# Fri3D_2020_Doodles.net
KiCad netlist of a schematic drawn in Altium Designer
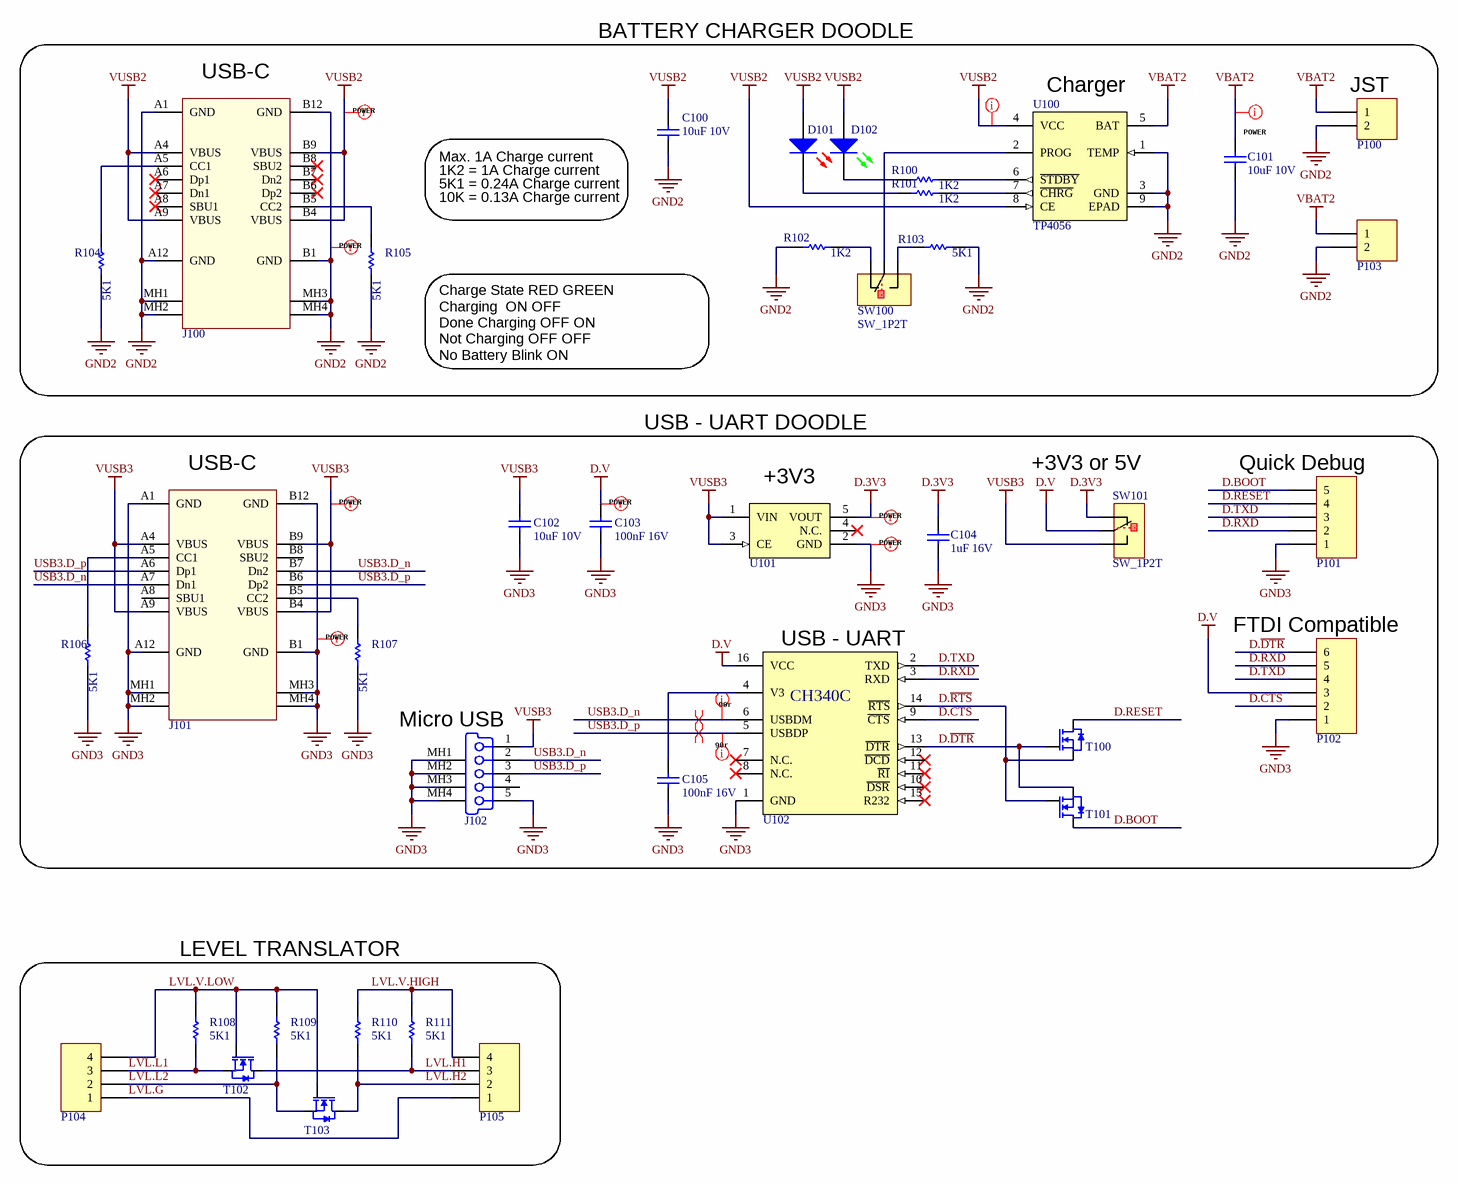
[diagram p0: Fri3D_2020_Doodles.SchDoc]

(export (version "E")
  (design (tool "Eeschema 10.0.6"))
  (components
    (comp (ref "C100")
      (value "10uF 10V")
      (footprint "C0805_N")
      (description "Capacitor Ceramic")
      (fields (field (name "Comment") "CAP_CERAMIC"))
      (libsource (lib "Phyx_Components") (part "CAP_CERAMIC"))
    )
    (comp (ref "C101")
      (value "10uF 10V")
      (footprint "C0805_N")
      (description "Capacitor Ceramic")
      (fields (field (name "Comment") "CAP_CERAMIC"))
      (libsource (lib "Phyx_Components") (part "CAP_CERAMIC"))
    )
    (comp (ref "C102")
      (value "10uF 10V")
      (footprint "C0805_N")
      (description "Capacitor Ceramic")
      (fields (field (name "Comment") "CAP_CERAMIC"))
      (libsource (lib "Phyx_Components") (part "CAP_CERAMIC"))
    )
    (comp (ref "C103")
      (value "100nF 16V")
      (footprint "C0603_N")
      (description "Capacitor Ceramic")
      (libsource (lib "Phyx_Components") (part "CAP_CERAMIC"))
    )
    (comp (ref "C104")
      (value "1uF 16V")
      (footprint "C0603_N")
      (description "Capacitor Ceramic")
      (fields (field (name "Comment") "CAP_CERAMIC"))
      (libsource (lib "Phyx_Components") (part "CAP_CERAMIC"))
    )
    (comp (ref "C105")
      (value "100nF 16V")
      (footprint "C0603_N")
      (description "Capacitor Ceramic")
      (libsource (lib "Phyx_Components") (part "CAP_CERAMIC"))
    )
    (comp (ref "D101")
      (value "Default 0805 Red LED")
      (footprint "LED_0805_RD")
      (description "=Description")
      (libsource (lib "Phyx_Components") (part "LED_RED"))
    )
    (comp (ref "D102")
      (value "Default 0805 Green LED")
      (footprint "LED_0805_GR")
      (description "=Description")
      (libsource (lib "Phyx_Components") (part "LED_GREEN"))
    )
    (comp (ref "J100")
      (value "USB 2.0 C Reversible Receptacle Horizontal")
      (footprint "HRO_TYPE-C-31-M-12")
      (libsource (lib "Phyx_Components") (part "USB_C_16_4"))
    )
    (comp (ref "J101")
      (value "USB 2.0 C Reversible Receptacle Horizontal")
      (footprint "HRO_TYPE-C-31-M-12")
      (libsource (lib "Phyx_Components") (part "USB_C_16_4"))
    )
    (comp (ref "J102")
      (value "XKB U254-051T-4BH81-S2S Micro USB")
      (footprint "XKB_U254-051T-4BH81-S2S")
      (libsource (lib "Phyx_Components") (part "USB_OTG_Mini-B"))
    )
    (comp (ref "P100")
      (value "Header 2.0mm Shrouded 2")
      (footprint "WE_620102131822")
      (libsource (lib "Phyx_Components") (part "Header 2"))
    )
    (comp (ref "P101")
      (value "Header 1.0mm RA Shrouded 5")
      (footprint "WE_665105131822")
      (libsource (lib "Phyx_Components") (part "Header 5"))
    )
    (comp (ref "P102")
      (value "Header 6")
      (footprint "HDR1X6")
      (libsource (lib "Phyx_Components") (part "Header 6"))
    )
    (comp (ref "P103")
      (value "Header 2")
      (footprint "HDR1X2")
      (libsource (lib "Phyx_Components") (part "Header 2"))
    )
    (comp (ref "P104")
      (value "Header 4")
      (footprint "HDR1X4")
      (libsource (lib "Phyx_Components") (part "Header 4"))
    )
    (comp (ref "P105") (value "Header 4") (footprint "HDR1X4") (libsource (lib "") (part "Header 4_1")))
    (comp (ref "R100")
      (value "1K2")
      (footprint "R0603_N")
      (fields (field (name "Comment") "RESISTOR"))
      (libsource (lib "Phyx_Components") (part "RESISTOR"))
    )
    (comp (ref "R101")
      (value "1K2")
      (footprint "R0603_N")
      (fields (field (name "Comment") "RESISTOR"))
      (libsource (lib "Phyx_Components") (part "RESISTOR"))
    )
    (comp (ref "R102")
      (value "1K2")
      (footprint "R0603_N")
      (fields (field (name "Comment") "RESISTOR"))
      (libsource (lib "Phyx_Components") (part "RESISTOR"))
    )
    (comp (ref "R103")
      (value "5K1")
      (footprint "R0603_N")
      (fields (field (name "Comment") "RESISTOR"))
      (libsource (lib "Phyx_Components") (part "RESISTOR"))
    )
    (comp (ref "R104")
      (value "5K1")
      (footprint "R0603_N")
      (fields (field (name "Comment") "RESISTOR"))
      (libsource (lib "Phyx_Components") (part "RESISTOR"))
    )
    (comp (ref "R105")
      (value "5K1")
      (footprint "R0603_N")
      (fields (field (name "Comment") "RESISTOR"))
      (libsource (lib "Phyx_Components") (part "RESISTOR"))
    )
    (comp (ref "R106")
      (value "5K1")
      (footprint "R0603_N")
      (fields (field (name "Comment") "RESISTOR"))
      (libsource (lib "Phyx_Components") (part "RESISTOR"))
    )
    (comp (ref "R107")
      (value "5K1")
      (footprint "R0603_N")
      (fields (field (name "Comment") "RESISTOR"))
      (libsource (lib "Phyx_Components") (part "RESISTOR"))
    )
    (comp (ref "R108")
      (value "5K1")
      (footprint "R0603_N")
      (fields (field (name "Comment") "RESISTOR"))
      (libsource (lib "Phyx_Components") (part "RESISTOR"))
    )
    (comp (ref "R109")
      (value "5K1")
      (footprint "R0603_N")
      (fields (field (name "Comment") "RESISTOR"))
      (libsource (lib "Phyx_Components") (part "RESISTOR"))
    )
    (comp (ref "R110")
      (value "5K1")
      (footprint "R0603_N")
      (fields (field (name "Comment") "RESISTOR"))
      (libsource (lib "Phyx_Components") (part "RESISTOR"))
    )
    (comp (ref "R111")
      (value "5K1")
      (footprint "R0603_N")
      (fields (field (name "Comment") "RESISTOR"))
      (libsource (lib "Phyx_Components") (part "RESISTOR"))
    )
    (comp (ref "SW100")
      (value "SW_1P2T")
      (footprint "WE_450404015514")
      (libsource (lib "Phyx_Components") (part "SW_1P2T"))
    )
    (comp (ref "SW101")
      (value "SW_1P2T")
      (footprint "WE_450404015514")
      (libsource (lib "") (part "SW_1P2T_1"))
    )
    (comp (ref "T100")
      (value "0.2A N-Ch MOSFET Vgs 3.2")
      (footprint "SOT23-3")
      (libsource (lib "Phyx_Components") (part "N_MOSFET_GSD"))
    )
    (comp (ref "T101")
      (value "0.2A N-Ch MOSFET Vgs 3.2")
      (footprint "SOT23-3")
      (libsource (lib "Phyx_Components") (part "N_MOSFET_GSD"))
    )
    (comp (ref "T102")
      (value "0.2A N-Ch MOSFET Vgs 3.2")
      (footprint "SOT23-3")
      (libsource (lib "Phyx_Components") (part "N_MOSFET_GSD"))
    )
    (comp (ref "T103")
      (value "0.2A N-Ch MOSFET Vgs 3.2")
      (footprint "SOT23-3")
      (libsource (lib "Phyx_Components") (part "N_MOSFET_GSD"))
    )
    (comp (ref "U100")
      (value "TP4056")
      (footprint "SOIC_N_8_TH")
      (description "=Description")
      (fields (field (name "Comment") "Single Cell LiIon charger max 1A"))
      (libsource (lib "Phyx_Components") (part "TP4056"))
    )
    (comp (ref "U101")
      (value "3V3 LDO 700mA 50mV")
      (footprint "SOT23-5")
      (description "=Designator")
      (libsource (lib "Phyx_Components") (part "XC6210_SOT"))
    )
    (comp (ref "U102")
      (value "USB to full UART with internal crystal")
      (footprint "SOIC_N_16")
      (description "=Description")
      (libsource (lib "Phyx_Components") (part "CH340C"))
    )
  )
  (nets
    (net (code "1") (name "/D.BOOT") (class "Default")
      (node (ref "P101") (pin "5") (pinfunction "5_5") (pintype "passive"))
      (node (ref "T101") (pin "3") (pinfunction "D_3") (pintype "passive"))
    )
    (net (code "2") (name "/D.RESET") (class "Default")
      (node (ref "P101") (pin "4") (pinfunction "4_4") (pintype "passive"))
      (node (ref "T100") (pin "3") (pinfunction "D_3") (pintype "passive"))
    )
    (net (code "3") (name "/D.RXD") (class "Default")
      (node (ref "P101") (pin "2") (pinfunction "2_2") (pintype "passive"))
      (node (ref "P102") (pin "5") (pinfunction "5_5") (pintype "passive"))
      (node (ref "U102") (pin "3") (pinfunction "RXD_3") (pintype "input"))
    )
    (net (code "4") (name "/D.TXD") (class "Default")
      (node (ref "P101") (pin "3") (pinfunction "3_3") (pintype "passive"))
      (node (ref "P102") (pin "4") (pinfunction "4_4") (pintype "passive"))
      (node (ref "U102") (pin "2") (pinfunction "TXD_2") (pintype "output"))
    )
    (net (code "5") (name "/D.~{CTS}") (class "Default")
      (node (ref "P102") (pin "2") (pinfunction "2_2") (pintype "passive"))
      (node (ref "U102") (pin "9") (pinfunction "~{CTS}_9") (pintype "input"))
    )
    (net (code "6") (name "/D.~{DTR}") (class "Default")
      (node (ref "P102") (pin "6") (pinfunction "6_6") (pintype "passive"))
      (node (ref "T100") (pin "1") (pinfunction "G_1") (pintype "passive"))
      (node (ref "T101") (pin "2") (pinfunction "S_2") (pintype "passive"))
      (node (ref "U102") (pin "13") (pinfunction "~{DTR}_13") (pintype "output"))
    )
    (net (code "7") (name "/D.~{RTS}") (class "Default")
      (node (ref "T100") (pin "2") (pinfunction "S_2") (pintype "passive"))
      (node (ref "T101") (pin "1") (pinfunction "G_1") (pintype "passive"))
      (node (ref "U102") (pin "14") (pinfunction "~{RTS}_14") (pintype "output"))
    )
    (net (code "8") (name "/LVL.G") (class "Default")
      (node (ref "P104") (pin "1") (pinfunction "1_1") (pintype "passive"))
      (node (ref "P105") (pin "1") (pinfunction "1_1") (pintype "passive"))
    )
    (net (code "9") (name "/LVL.H1") (class "Default")
      (node (ref "P105") (pin "3") (pinfunction "3_3") (pintype "passive"))
      (node (ref "R111") (pin "2") (pinfunction "2_2") (pintype "passive"))
      (node (ref "T102") (pin "3") (pinfunction "D_3") (pintype "passive"))
    )
    (net (code "10") (name "/LVL.H2") (class "Default")
      (node (ref "P105") (pin "2") (pinfunction "2_2") (pintype "passive"))
      (node (ref "R110") (pin "2") (pinfunction "2_2") (pintype "passive"))
      (node (ref "T103") (pin "3") (pinfunction "D_3") (pintype "passive"))
    )
    (net (code "11") (name "/LVL.L1") (class "Default")
      (node (ref "P104") (pin "3") (pinfunction "3_3") (pintype "passive"))
      (node (ref "R108") (pin "2") (pinfunction "2_2") (pintype "passive"))
      (node (ref "T102") (pin "2") (pinfunction "S_2") (pintype "passive"))
    )
    (net (code "12") (name "/LVL.L2") (class "Default")
      (node (ref "P104") (pin "2") (pinfunction "2_2") (pintype "passive"))
      (node (ref "R109") (pin "2") (pinfunction "2_2") (pintype "passive"))
      (node (ref "T103") (pin "2") (pinfunction "S_2") (pintype "passive"))
    )
    (net (code "13") (name "/LVL.V.HIGH") (class "Default")
      (node (ref "P105") (pin "4") (pinfunction "4_4") (pintype "passive"))
      (node (ref "R110") (pin "1") (pinfunction "1_1") (pintype "passive"))
      (node (ref "R111") (pin "1") (pinfunction "1_1") (pintype "passive"))
    )
    (net (code "14") (name "/LVL.V.LOW") (class "Default")
      (node (ref "P104") (pin "4") (pinfunction "4_4") (pintype "passive"))
      (node (ref "R108") (pin "1") (pinfunction "1_1") (pintype "passive"))
      (node (ref "R109") (pin "1") (pinfunction "1_1") (pintype "passive"))
      (node (ref "T102") (pin "1") (pinfunction "G_1") (pintype "passive"))
      (node (ref "T103") (pin "1") (pinfunction "G_1") (pintype "passive"))
    )
    (net (code "15") (name "/USB3.D_n") (class "Default")
      (node (ref "J101") (pin "A7") (pinfunction "Dn1_A7") (pintype "passive"))
      (node (ref "J101") (pin "B7") (pinfunction "Dn2_B7") (pintype "passive"))
      (node (ref "J102") (pin "2") (pinfunction "D-_2") (pintype "passive"))
      (node (ref "U102") (pin "6") (pinfunction "USBDM_6") (pintype "passive"))
    )
    (net (code "16") (name "/USB3.D_p") (class "Default")
      (node (ref "J101") (pin "A6") (pinfunction "Dp1_A6") (pintype "passive"))
      (node (ref "J101") (pin "B6") (pinfunction "Dp2_B6") (pintype "passive"))
      (node (ref "J102") (pin "3") (pinfunction "D+_3") (pintype "passive"))
      (node (ref "U102") (pin "5") (pinfunction "USBDP_5") (pintype "passive"))
    )
    (net (code "17") (name "D.3V3") (class "Default")
      (node (ref "C104") (pin "1") (pinfunction "1_1") (pintype "passive"))
      (node (ref "SW101") (pin "1") (pinfunction "1_1") (pintype "passive"))
      (node (ref "U101") (pin "5") (pinfunction "VOUT_5") (pintype "power_in"))
    )
    (net (code "18") (name "D.V") (class "Default")
      (node (ref "C103") (pin "1") (pinfunction "1_1") (pintype "passive"))
      (node (ref "P102") (pin "3") (pinfunction "3_3") (pintype "passive"))
      (node (ref "SW101") (pin "2") (pinfunction "2_2") (pintype "passive"))
      (node (ref "U102") (pin "16") (pinfunction "VCC_16") (pintype "power_in"))
    )
    (net (code "19") (name "GND2") (class "Default")
      (node (ref "C100") (pin "2") (pinfunction "2_2") (pintype "passive"))
      (node (ref "C101") (pin "2") (pinfunction "2_2") (pintype "passive"))
      (node (ref "J100") (pin "A1") (pinfunction "GND_A1") (pintype "passive"))
      (node (ref "J100") (pin "A12") (pinfunction "GND_A12") (pintype "passive"))
      (node (ref "J100") (pin "B1") (pinfunction "GND_B1") (pintype "passive"))
      (node (ref "J100") (pin "B12") (pinfunction "GND_B12") (pintype "passive"))
      (node (ref "J100") (pin "MH1") (pinfunction "Tab_MH1") (pintype "passive"))
      (node (ref "J100") (pin "MH2") (pinfunction "Tab_MH2") (pintype "passive"))
      (node (ref "J100") (pin "MH3") (pinfunction "Tab_MH3") (pintype "passive"))
      (node (ref "J100") (pin "MH4") (pinfunction "Tab_MH4") (pintype "passive"))
      (node (ref "P100") (pin "2") (pinfunction "2_2") (pintype "passive"))
      (node (ref "P103") (pin "2") (pinfunction "2_2") (pintype "passive"))
      (node (ref "R102") (pin "2") (pinfunction "2_2") (pintype "passive"))
      (node (ref "R103") (pin "2") (pinfunction "2_2") (pintype "passive"))
      (node (ref "R104") (pin "2") (pinfunction "2_2") (pintype "passive"))
      (node (ref "R105") (pin "2") (pinfunction "2_2") (pintype "passive"))
      (node (ref "U100") (pin "1") (pinfunction "TEMP_1") (pintype "input"))
      (node (ref "U100") (pin "3") (pinfunction "GND_3") (pintype "power_in"))
      (node (ref "U100") (pin "9") (pinfunction "EPAD_9") (pintype "power_in"))
    )
    (net (code "20") (name "GND3") (class "Default")
      (node (ref "C102") (pin "2") (pinfunction "2_2") (pintype "passive"))
      (node (ref "C103") (pin "2") (pinfunction "2_2") (pintype "passive"))
      (node (ref "C104") (pin "2") (pinfunction "2_2") (pintype "passive"))
      (node (ref "C105") (pin "2") (pinfunction "2_2") (pintype "passive"))
      (node (ref "J101") (pin "A1") (pinfunction "GND_A1") (pintype "passive"))
      (node (ref "J101") (pin "A12") (pinfunction "GND_A12") (pintype "passive"))
      (node (ref "J101") (pin "B1") (pinfunction "GND_B1") (pintype "passive"))
      (node (ref "J101") (pin "B12") (pinfunction "GND_B12") (pintype "passive"))
      (node (ref "J101") (pin "MH1") (pinfunction "Tab_MH1") (pintype "passive"))
      (node (ref "J101") (pin "MH2") (pinfunction "Tab_MH2") (pintype "passive"))
      (node (ref "J101") (pin "MH3") (pinfunction "Tab_MH3") (pintype "passive"))
      (node (ref "J101") (pin "MH4") (pinfunction "Tab_MH4") (pintype "passive"))
      (node (ref "J102") (pin "5") (pinfunction "GND_5") (pintype "passive"))
      (node (ref "J102") (pin "MH1") (pinfunction "Tab_MH1") (pintype "passive"))
      (node (ref "J102") (pin "MH2") (pinfunction "Tab_MH2") (pintype "passive"))
      (node (ref "J102") (pin "MH3") (pinfunction "Tab_MH3") (pintype "passive"))
      (node (ref "J102") (pin "MH4") (pinfunction "Tab_MH4") (pintype "passive"))
      (node (ref "P101") (pin "1") (pinfunction "1_1") (pintype "passive"))
      (node (ref "P102") (pin "1") (pinfunction "1_1") (pintype "passive"))
      (node (ref "R106") (pin "2") (pinfunction "2_2") (pintype "passive"))
      (node (ref "R107") (pin "2") (pinfunction "2_2") (pintype "passive"))
      (node (ref "U101") (pin "2") (pinfunction "GND_2") (pintype "power_in"))
      (node (ref "U102") (pin "1") (pinfunction "GND_1") (pintype "power_in"))
    )
    (net (code "21") (name "Net-(D101-K)") (class "Default")
      (node (ref "D101") (pin "2") (pinfunction "K_2") (pintype "passive"))
      (node (ref "R101") (pin "1") (pinfunction "1_1") (pintype "passive"))
    )
    (net (code "22") (name "Net-(D102-K)") (class "Default")
      (node (ref "D102") (pin "2") (pinfunction "K_2") (pintype "passive"))
      (node (ref "R100") (pin "1") (pinfunction "1_1") (pintype "passive"))
    )
    (net (code "23") (name "Net-(J100-CC1)") (class "Default")
      (node (ref "J100") (pin "A5") (pinfunction "CC1_A5") (pintype "passive"))
      (node (ref "R104") (pin "1") (pinfunction "1_1") (pintype "passive"))
    )
    (net (code "24") (name "Net-(J100-CC2)") (class "Default")
      (node (ref "J100") (pin "B5") (pinfunction "CC2_B5") (pintype "passive"))
      (node (ref "R105") (pin "1") (pinfunction "1_1") (pintype "passive"))
    )
    (net (code "25") (name "Net-(J101-CC1)") (class "Default")
      (node (ref "J101") (pin "A5") (pinfunction "CC1_A5") (pintype "passive"))
      (node (ref "R106") (pin "1") (pinfunction "1_1") (pintype "passive"))
    )
    (net (code "26") (name "Net-(J101-CC2)") (class "Default")
      (node (ref "J101") (pin "B5") (pinfunction "CC2_B5") (pintype "passive"))
      (node (ref "R107") (pin "1") (pinfunction "1_1") (pintype "passive"))
    )
    (net (code "27") (name "Net-(R102-Pad1)") (class "Default")
      (node (ref "R102") (pin "1") (pinfunction "1_1") (pintype "passive"))
      (node (ref "SW100") (pin "1") (pinfunction "1_1") (pintype "passive"))
    )
    (net (code "28") (name "Net-(R103-Pad1)") (class "Default")
      (node (ref "R103") (pin "1") (pinfunction "1_1") (pintype "passive"))
      (node (ref "SW100") (pin "3") (pinfunction "3_3") (pintype "passive"))
    )
    (net (code "29") (name "Net-(U100-PROG)") (class "Default")
      (node (ref "SW100") (pin "2") (pinfunction "2_2") (pintype "passive"))
      (node (ref "U100") (pin "2") (pinfunction "PROG_2") (pintype "passive"))
    )
    (net (code "30") (name "Net-(U100-~{CHRG})") (class "Default")
      (node (ref "R101") (pin "2") (pinfunction "2_2") (pintype "passive"))
      (node (ref "U100") (pin "7") (pinfunction "~{CHRG}_7") (pintype "output"))
    )
    (net (code "31") (name "Net-(U100-~{STDBY})") (class "Default")
      (node (ref "R100") (pin "2") (pinfunction "2_2") (pintype "passive"))
      (node (ref "U100") (pin "6") (pinfunction "~{STDBY}_6") (pintype "output"))
    )
    (net (code "32") (name "Net-(U102-V3)") (class "Default")
      (node (ref "C105") (pin "1") (pinfunction "1_1") (pintype "passive"))
      (node (ref "U102") (pin "4") (pinfunction "V3_4") (pintype "power_in"))
    )
    (net (code "33") (name "VBAT2") (class "Default")
      (node (ref "C101") (pin "1") (pinfunction "1_1") (pintype "passive"))
      (node (ref "P100") (pin "1") (pinfunction "1_1") (pintype "passive"))
      (node (ref "P103") (pin "1") (pinfunction "1_1") (pintype "passive"))
      (node (ref "U100") (pin "5") (pinfunction "BAT_5") (pintype "power_in"))
    )
    (net (code "34") (name "VUSB2") (class "Default")
      (node (ref "C100") (pin "1") (pinfunction "1_1") (pintype "passive"))
      (node (ref "D101") (pin "1") (pinfunction "A_1") (pintype "passive"))
      (node (ref "D102") (pin "1") (pinfunction "A_1") (pintype "passive"))
      (node (ref "J100") (pin "A4") (pinfunction "VBUS_A4") (pintype "passive"))
      (node (ref "J100") (pin "A9") (pinfunction "VBUS_A9") (pintype "passive"))
      (node (ref "J100") (pin "B4") (pinfunction "VBUS_B4") (pintype "passive"))
      (node (ref "J100") (pin "B9") (pinfunction "VBUS_B9") (pintype "passive"))
      (node (ref "U100") (pin "4") (pinfunction "VCC_4") (pintype "power_in"))
      (node (ref "U100") (pin "8") (pinfunction "CE_8") (pintype "input"))
    )
    (net (code "35") (name "VUSB3") (class "Default")
      (node (ref "C102") (pin "1") (pinfunction "1_1") (pintype "passive"))
      (node (ref "J101") (pin "A4") (pinfunction "VBUS_A4") (pintype "passive"))
      (node (ref "J101") (pin "A9") (pinfunction "VBUS_A9") (pintype "passive"))
      (node (ref "J101") (pin "B4") (pinfunction "VBUS_B4") (pintype "passive"))
      (node (ref "J101") (pin "B9") (pinfunction "VBUS_B9") (pintype "passive"))
      (node (ref "J102") (pin "1") (pinfunction "V_BUS_(5V)_1") (pintype "passive"))
      (node (ref "SW101") (pin "3") (pinfunction "3_3") (pintype "passive"))
      (node (ref "U101") (pin "1") (pinfunction "VIN_1") (pintype "power_in"))
      (node (ref "U101") (pin "3") (pinfunction "CE_3") (pintype "input"))
    )
    (net (code "36") (name "unconnected-(J100-Dn1-PadA7)") (class "Default")
      (node (ref "J100") (pin "A7") (pinfunction "Dn1_A7") (pintype "passive+no_connect"))
    )
    (net (code "37") (name "unconnected-(J100-Dn2-PadB7)") (class "Default")
      (node (ref "J100") (pin "B7") (pinfunction "Dn2_B7") (pintype "passive+no_connect"))
    )
    (net (code "38") (name "unconnected-(J100-Dp1-PadA6)") (class "Default")
      (node (ref "J100") (pin "A6") (pinfunction "Dp1_A6") (pintype "passive+no_connect"))
    )
    (net (code "39") (name "unconnected-(J100-Dp2-PadB6)") (class "Default")
      (node (ref "J100") (pin "B6") (pinfunction "Dp2_B6") (pintype "passive+no_connect"))
    )
    (net (code "40") (name "unconnected-(J100-SBU1-PadA8)") (class "Default")
      (node (ref "J100") (pin "A8") (pinfunction "SBU1_A8") (pintype "passive+no_connect"))
    )
    (net (code "41") (name "unconnected-(J100-SBU2-PadB8)") (class "Default")
      (node (ref "J100") (pin "B8") (pinfunction "SBU2_B8") (pintype "passive+no_connect"))
    )
    (net (code "42") (name "unconnected-(J101-SBU1-PadA8)") (class "Default")
      (node (ref "J101") (pin "A8") (pinfunction "SBU1_A8") (pintype "passive"))
    )
    (net (code "43") (name "unconnected-(J101-SBU2-PadB8)") (class "Default")
      (node (ref "J101") (pin "B8") (pinfunction "SBU2_B8") (pintype "passive"))
    )
    (net (code "44") (name "unconnected-(J102-NC-Pad4)") (class "Default")
      (node (ref "J102") (pin "4") (pinfunction "NC_4") (pintype "passive"))
    )
    (net (code "45") (name "unconnected-(U101-N.C.-Pad4)") (class "Default")
      (node (ref "U101") (pin "4") (pinfunction "N.C._4") (pintype "passive+no_connect"))
    )
    (net (code "46") (name "unconnected-(U102-N.C.-Pad7)") (class "Default")
      (node (ref "U102") (pin "7") (pinfunction "N.C._7") (pintype "passive+no_connect"))
    )
    (net (code "47") (name "unconnected-(U102-N.C.-Pad8)") (class "Default")
      (node (ref "U102") (pin "8") (pinfunction "N.C._8") (pintype "passive+no_connect"))
    )
    (net (code "48") (name "unconnected-(U102-R232-Pad15)") (class "Default")
      (node (ref "U102") (pin "15") (pinfunction "R232_15") (pintype "input+no_connect"))
    )
    (net (code "49") (name "unconnected-(U102-~{DCD}-Pad12)") (class "Default")
      (node (ref "U102") (pin "12") (pinfunction "~{DCD}_12") (pintype "input+no_connect"))
    )
    (net (code "50") (name "unconnected-(U102-~{DSR}-Pad10)") (class "Default")
      (node (ref "U102") (pin "10") (pinfunction "~{DSR}_10") (pintype "input+no_connect"))
    )
    (net (code "51") (name "unconnected-(U102-~{RI}-Pad11)") (class "Default")
      (node (ref "U102") (pin "11") (pinfunction "~{RI}_11") (pintype "input+no_connect"))
    )
  )
)
